# Varmo_Screen.net
KiCad netlist of a schematic drawn in EAGLE
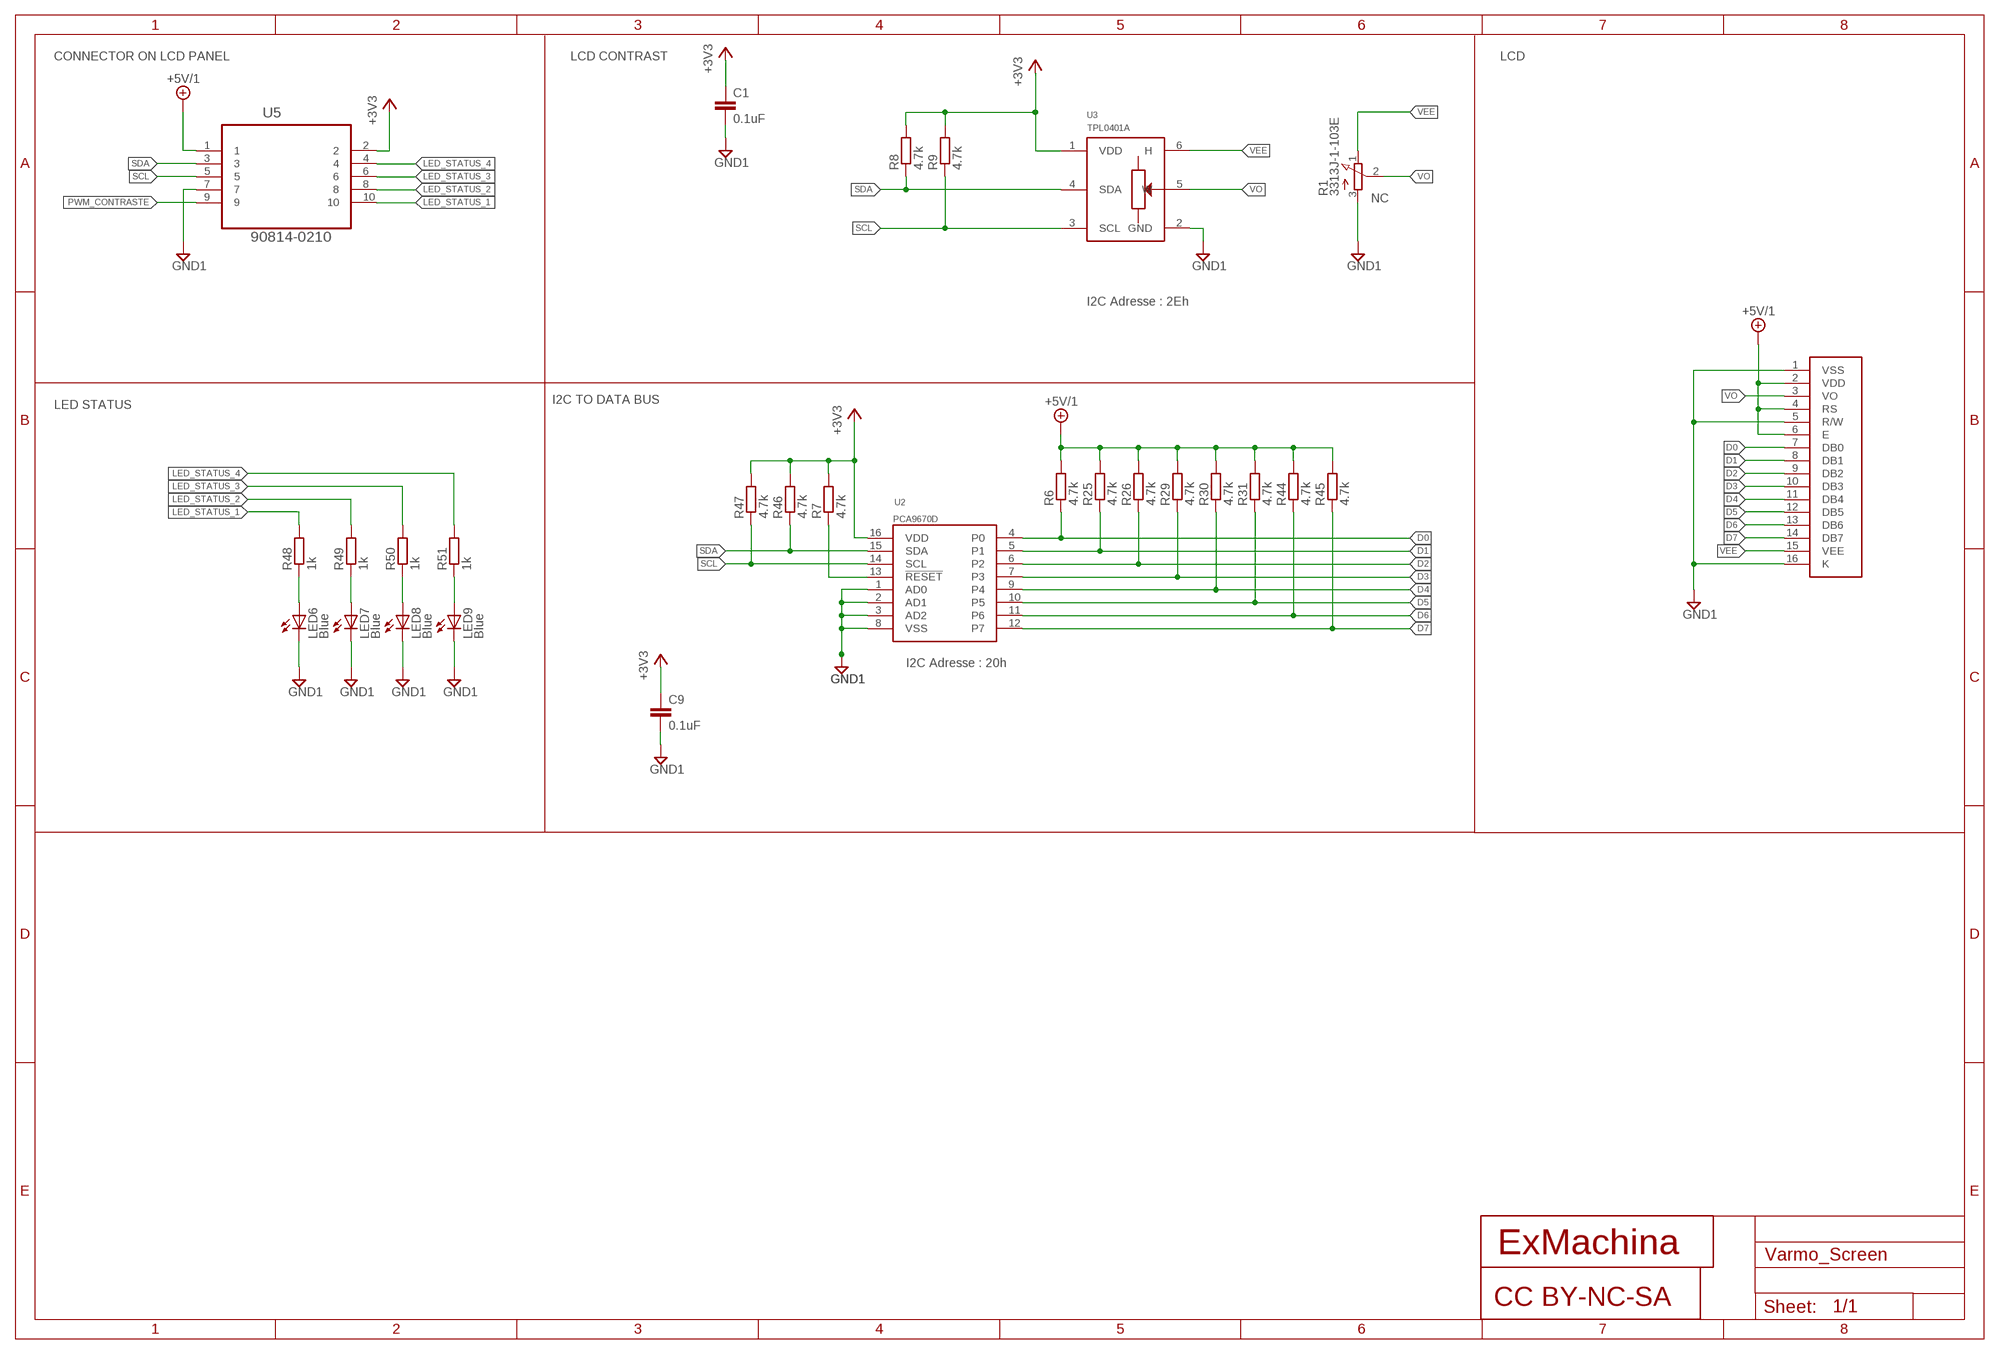
[diagram p0: schematic, sheet 1]

(export (version "E")
  (design (tool "Eeschema 10.0.6"))
  (components
    (comp (ref "C1")
      (value "0.1uF")
      (footprint "eagle-import:C0603")
      (libsource (lib "eagle-import") (part "C-EUC0603"))
    )
    (comp (ref "C9")
      (value "0.1uF")
      (footprint "eagle-import:C0603")
      (libsource (lib "eagle-import") (part "C-EUC0603"))
    )
    (comp (ref "LCD1")
      (value "MC41605A12W")
      (footprint "eagle-import:CONNECTOR")
      (libsource (lib "eagle-import") (part "MC41605A12W"))
    )
    (comp (ref "LED6")
      (value "Blue")
      (footprint "eagle-import:CHIP-LED0603")
      (libsource (lib "eagle-import") (part "LEDCHIP-LED0603"))
    )
    (comp (ref "LED7")
      (value "Blue")
      (footprint "eagle-import:CHIP-LED0603")
      (libsource (lib "eagle-import") (part "LEDCHIP-LED0603"))
    )
    (comp (ref "LED8")
      (value "Blue")
      (footprint "eagle-import:CHIP-LED0603")
      (libsource (lib "eagle-import") (part "LEDCHIP-LED0603"))
    )
    (comp (ref "LED9")
      (value "Blue")
      (footprint "eagle-import:CHIP-LED0603")
      (libsource (lib "eagle-import") (part "LEDCHIP-LED0603"))
    )
    (comp (ref "R1")
      (value "3313J-1-103E")
      (footprint "eagle-import:3313J")
      (libsource (lib "eagle-import") (part "3313J-1-103E"))
    )
    (comp (ref "R6")
      (value "4.7k")
      (footprint "eagle-import:R0603")
      (libsource (lib "eagle-import") (part "R-EU_R0603"))
    )
    (comp (ref "R7")
      (value "4.7k")
      (footprint "eagle-import:R0603")
      (libsource (lib "eagle-import") (part "R-EU_R0603"))
    )
    (comp (ref "R8")
      (value "4.7k")
      (footprint "eagle-import:R0603")
      (libsource (lib "eagle-import") (part "R-EU_R0603"))
    )
    (comp (ref "R9")
      (value "4.7k")
      (footprint "eagle-import:R0603")
      (libsource (lib "eagle-import") (part "R-EU_R0603"))
    )
    (comp (ref "R25")
      (value "4.7k")
      (footprint "eagle-import:R0603")
      (libsource (lib "eagle-import") (part "R-EU_R0603"))
    )
    (comp (ref "R26")
      (value "4.7k")
      (footprint "eagle-import:R0603")
      (libsource (lib "eagle-import") (part "R-EU_R0603"))
    )
    (comp (ref "R29")
      (value "4.7k")
      (footprint "eagle-import:R0603")
      (libsource (lib "eagle-import") (part "R-EU_R0603"))
    )
    (comp (ref "R30")
      (value "4.7k")
      (footprint "eagle-import:R0603")
      (libsource (lib "eagle-import") (part "R-EU_R0603"))
    )
    (comp (ref "R31")
      (value "4.7k")
      (footprint "eagle-import:R0603")
      (libsource (lib "eagle-import") (part "R-EU_R0603"))
    )
    (comp (ref "R44")
      (value "4.7k")
      (footprint "eagle-import:R0603")
      (libsource (lib "eagle-import") (part "R-EU_R0603"))
    )
    (comp (ref "R45")
      (value "4.7k")
      (footprint "eagle-import:R0603")
      (libsource (lib "eagle-import") (part "R-EU_R0603"))
    )
    (comp (ref "R46")
      (value "4.7k")
      (footprint "eagle-import:R0603")
      (libsource (lib "eagle-import") (part "R-EU_R0603"))
    )
    (comp (ref "R47")
      (value "4.7k")
      (footprint "eagle-import:R0603")
      (libsource (lib "eagle-import") (part "R-EU_R0603"))
    )
    (comp (ref "R48")
      (value "1k")
      (footprint "eagle-import:R0603")
      (libsource (lib "eagle-import") (part "R-EU_R0603"))
    )
    (comp (ref "R49")
      (value "1k")
      (footprint "eagle-import:R0603")
      (libsource (lib "eagle-import") (part "R-EU_R0603"))
    )
    (comp (ref "R50")
      (value "1k")
      (footprint "eagle-import:R0603")
      (libsource (lib "eagle-import") (part "R-EU_R0603"))
    )
    (comp (ref "R51")
      (value "1k")
      (footprint "eagle-import:R0603")
      (libsource (lib "eagle-import") (part "R-EU_R0603"))
    )
    (comp (ref "U$5")
      (value "CC-BY-NC-SA")
      (footprint "eagle-import:CC-BY-NC-SA")
      (libsource (lib "eagle-import") (part "CC-BY-NC-SA"))
    )
    (comp (ref "U$7")
      (value "EXMACHINA-LOGO-NAME")
      (footprint "eagle-import:EXM-LOGO-BASELINE")
      (libsource (lib "eagle-import") (part "EXMACHINA-LOGO-NAME"))
    )
    (comp (ref "U2")
      (value "PCA9670D")
      (footprint "eagle-import:SOT162-1")
      (libsource (lib "eagle-import") (part "PCA9670D"))
    )
    (comp (ref "U3")
      (value "TPL0401A")
      (footprint "eagle-import:SC-70-DCK")
      (libsource (lib "eagle-import") (part "TPL0401A"))
    )
    (comp (ref "U5")
      (value "90814-0210")
      (footprint "eagle-import:MOLEX_90814-0210")
      (libsource (lib "eagle-import") (part "90814-0210"))
    )
  )
  (nets
    (net (code "1") (name "+3V3") (class "Default")
      (node (ref "C1") (pin "1") (pinfunction "1_1") (pintype "passive"))
      (node (ref "C9") (pin "1") (pinfunction "1_1") (pintype "passive"))
      (node (ref "R46") (pin "2") (pinfunction "2_2") (pintype "passive"))
      (node (ref "R47") (pin "2") (pinfunction "2_2") (pintype "passive"))
      (node (ref "R7") (pin "2") (pinfunction "2_2") (pintype "passive"))
      (node (ref "R8") (pin "2") (pinfunction "2_2") (pintype "passive"))
      (node (ref "R9") (pin "2") (pinfunction "2_2") (pintype "passive"))
      (node (ref "U2") (pin "16") (pinfunction "VDD_16") (pintype "bidirectional"))
      (node (ref "U3") (pin "1") (pinfunction "VDD_1") (pintype "power_in"))
      (node (ref "U5") (pin "2") (pinfunction "2_2") (pintype "passive"))
    )
    (net (code "2") (name "+5V{slash}1") (class "Default")
      (node (ref "LCD1") (pin "2") (pinfunction "VDD_2") (pintype "bidirectional"))
      (node (ref "LCD1") (pin "4") (pinfunction "RS_4") (pintype "bidirectional"))
      (node (ref "LCD1") (pin "6") (pinfunction "E_6") (pintype "bidirectional"))
      (node (ref "R25") (pin "2") (pinfunction "2_2") (pintype "passive"))
      (node (ref "R26") (pin "2") (pinfunction "2_2") (pintype "passive"))
      (node (ref "R29") (pin "2") (pinfunction "2_2") (pintype "passive"))
      (node (ref "R30") (pin "2") (pinfunction "2_2") (pintype "passive"))
      (node (ref "R31") (pin "2") (pinfunction "2_2") (pintype "passive"))
      (node (ref "R44") (pin "2") (pinfunction "2_2") (pintype "passive"))
      (node (ref "R45") (pin "2") (pinfunction "2_2") (pintype "passive"))
      (node (ref "R6") (pin "2") (pinfunction "2_2") (pintype "passive"))
      (node (ref "U5") (pin "1") (pinfunction "1_1") (pintype "passive"))
    )
    (net (code "3") (name "D0") (class "Default")
      (node (ref "LCD1") (pin "7") (pinfunction "DB0_7") (pintype "bidirectional"))
      (node (ref "R6") (pin "1") (pinfunction "1_1") (pintype "passive"))
      (node (ref "U2") (pin "4") (pinfunction "P0_4") (pintype "bidirectional"))
    )
    (net (code "4") (name "D1") (class "Default")
      (node (ref "LCD1") (pin "8") (pinfunction "DB1_8") (pintype "bidirectional"))
      (node (ref "R25") (pin "1") (pinfunction "1_1") (pintype "passive"))
      (node (ref "U2") (pin "5") (pinfunction "P1_5") (pintype "bidirectional"))
    )
    (net (code "5") (name "D2") (class "Default")
      (node (ref "LCD1") (pin "9") (pinfunction "DB2_9") (pintype "bidirectional"))
      (node (ref "R26") (pin "1") (pinfunction "1_1") (pintype "passive"))
      (node (ref "U2") (pin "6") (pinfunction "P2_6") (pintype "bidirectional"))
    )
    (net (code "6") (name "D3") (class "Default")
      (node (ref "LCD1") (pin "10") (pinfunction "DB3_10") (pintype "bidirectional"))
      (node (ref "R29") (pin "1") (pinfunction "1_1") (pintype "passive"))
      (node (ref "U2") (pin "7") (pinfunction "P3_7") (pintype "bidirectional"))
    )
    (net (code "7") (name "D4") (class "Default")
      (node (ref "LCD1") (pin "11") (pinfunction "DB4_11") (pintype "bidirectional"))
      (node (ref "R30") (pin "1") (pinfunction "1_1") (pintype "passive"))
      (node (ref "U2") (pin "9") (pinfunction "P4_9") (pintype "bidirectional"))
    )
    (net (code "8") (name "D5") (class "Default")
      (node (ref "LCD1") (pin "12") (pinfunction "DB5_12") (pintype "bidirectional"))
      (node (ref "R31") (pin "1") (pinfunction "1_1") (pintype "passive"))
      (node (ref "U2") (pin "10") (pinfunction "P5_10") (pintype "bidirectional"))
    )
    (net (code "9") (name "D6") (class "Default")
      (node (ref "LCD1") (pin "13") (pinfunction "DB6_13") (pintype "bidirectional"))
      (node (ref "R44") (pin "1") (pinfunction "1_1") (pintype "passive"))
      (node (ref "U2") (pin "11") (pinfunction "P6_11") (pintype "bidirectional"))
    )
    (net (code "10") (name "D7") (class "Default")
      (node (ref "LCD1") (pin "14") (pinfunction "DB7_14") (pintype "bidirectional"))
      (node (ref "R45") (pin "1") (pinfunction "1_1") (pintype "passive"))
      (node (ref "U2") (pin "12") (pinfunction "P7_12") (pintype "bidirectional"))
    )
    (net (code "11") (name "GND1") (class "Default")
      (node (ref "C1") (pin "2") (pinfunction "2_2") (pintype "passive"))
      (node (ref "C9") (pin "2") (pinfunction "2_2") (pintype "passive"))
      (node (ref "LCD1") (pin "1") (pinfunction "VSS_1") (pintype "bidirectional"))
      (node (ref "LCD1") (pin "16") (pinfunction "K_16") (pintype "bidirectional"))
      (node (ref "LCD1") (pin "5") (pinfunction "R/W_5") (pintype "bidirectional"))
      (node (ref "LED6") (pin "C") (pinfunction "C_C") (pintype "passive"))
      (node (ref "LED7") (pin "C") (pinfunction "C_C") (pintype "passive"))
      (node (ref "LED8") (pin "C") (pinfunction "C_C") (pintype "passive"))
      (node (ref "LED9") (pin "C") (pinfunction "C_C") (pintype "passive"))
      (node (ref "R1") (pin "3") (pinfunction "A_3") (pintype "passive"))
      (node (ref "U2") (pin "1") (pinfunction "AD0_1") (pintype "bidirectional"))
      (node (ref "U2") (pin "2") (pinfunction "AD1_2") (pintype "bidirectional"))
      (node (ref "U2") (pin "3") (pinfunction "AD2_3") (pintype "bidirectional"))
      (node (ref "U2") (pin "8") (pinfunction "VSS_8") (pintype "bidirectional"))
      (node (ref "U3") (pin "2") (pinfunction "GND_2") (pintype "power_in"))
      (node (ref "U5") (pin "7") (pinfunction "7_7") (pintype "passive"))
    )
    (net (code "12") (name "LED_STATUS_1") (class "Default")
      (node (ref "R48") (pin "2") (pinfunction "2_2") (pintype "passive"))
      (node (ref "U5") (pin "10") (pinfunction "10_10") (pintype "passive"))
    )
    (net (code "13") (name "LED_STATUS_2") (class "Default")
      (node (ref "R49") (pin "2") (pinfunction "2_2") (pintype "passive"))
      (node (ref "U5") (pin "8") (pinfunction "8_8") (pintype "passive"))
    )
    (net (code "14") (name "LED_STATUS_3") (class "Default")
      (node (ref "R50") (pin "2") (pinfunction "2_2") (pintype "passive"))
      (node (ref "U5") (pin "6") (pinfunction "6_6") (pintype "passive"))
    )
    (net (code "15") (name "LED_STATUS_4") (class "Default")
      (node (ref "R51") (pin "2") (pinfunction "2_2") (pintype "passive"))
      (node (ref "U5") (pin "4") (pinfunction "4_4") (pintype "passive"))
    )
    (net (code "16") (name "Net-(LED6-PadA)") (class "Default")
      (node (ref "LED6") (pin "A") (pinfunction "A_A") (pintype "passive"))
      (node (ref "R48") (pin "1") (pinfunction "1_1") (pintype "passive"))
    )
    (net (code "17") (name "Net-(LED7-PadA)") (class "Default")
      (node (ref "LED7") (pin "A") (pinfunction "A_A") (pintype "passive"))
      (node (ref "R49") (pin "1") (pinfunction "1_1") (pintype "passive"))
    )
    (net (code "18") (name "Net-(LED8-PadA)") (class "Default")
      (node (ref "LED8") (pin "A") (pinfunction "A_A") (pintype "passive"))
      (node (ref "R50") (pin "1") (pinfunction "1_1") (pintype "passive"))
    )
    (net (code "19") (name "Net-(LED9-PadA)") (class "Default")
      (node (ref "LED9") (pin "A") (pinfunction "A_A") (pintype "passive"))
      (node (ref "R51") (pin "1") (pinfunction "1_1") (pintype "passive"))
    )
    (net (code "20") (name "Net-(U2-~{RESET})") (class "Default")
      (node (ref "R7") (pin "1") (pinfunction "1_1") (pintype "passive"))
      (node (ref "U2") (pin "13") (pinfunction "~{RESET}_13") (pintype "bidirectional"))
    )
    (net (code "21") (name "PWM_CONTRASTE") (class "Default")
      (node (ref "U5") (pin "9") (pinfunction "9_9") (pintype "passive"))
    )
    (net (code "22") (name "SCL") (class "Default")
      (node (ref "R47") (pin "1") (pinfunction "1_1") (pintype "passive"))
      (node (ref "R9") (pin "1") (pinfunction "1_1") (pintype "passive"))
      (node (ref "U2") (pin "14") (pinfunction "SCL_14") (pintype "bidirectional"))
      (node (ref "U3") (pin "3") (pinfunction "SCL_3") (pintype "bidirectional"))
      (node (ref "U5") (pin "5") (pinfunction "5_5") (pintype "passive"))
    )
    (net (code "23") (name "SDA") (class "Default")
      (node (ref "R46") (pin "1") (pinfunction "1_1") (pintype "passive"))
      (node (ref "R8") (pin "1") (pinfunction "1_1") (pintype "passive"))
      (node (ref "U2") (pin "15") (pinfunction "SDA_15") (pintype "bidirectional"))
      (node (ref "U3") (pin "4") (pinfunction "SDA_4") (pintype "bidirectional"))
      (node (ref "U5") (pin "3") (pinfunction "3_3") (pintype "passive"))
    )
    (net (code "24") (name "VEE") (class "Default")
      (node (ref "LCD1") (pin "15") (pinfunction "VEE_15") (pintype "bidirectional"))
      (node (ref "R1") (pin "1") (pinfunction "E_1") (pintype "passive"))
      (node (ref "U3") (pin "6") (pinfunction "H_6") (pintype "bidirectional"))
    )
    (net (code "25") (name "VO") (class "Default")
      (node (ref "LCD1") (pin "3") (pinfunction "VO_3") (pintype "bidirectional"))
      (node (ref "R1") (pin "2") (pinfunction "S_2") (pintype "passive"))
      (node (ref "U3") (pin "5") (pinfunction "W_5") (pintype "bidirectional"))
    )
  )
)
